# Display7Seg.net
KiCad netlist of a schematic drawn in Altium Designer
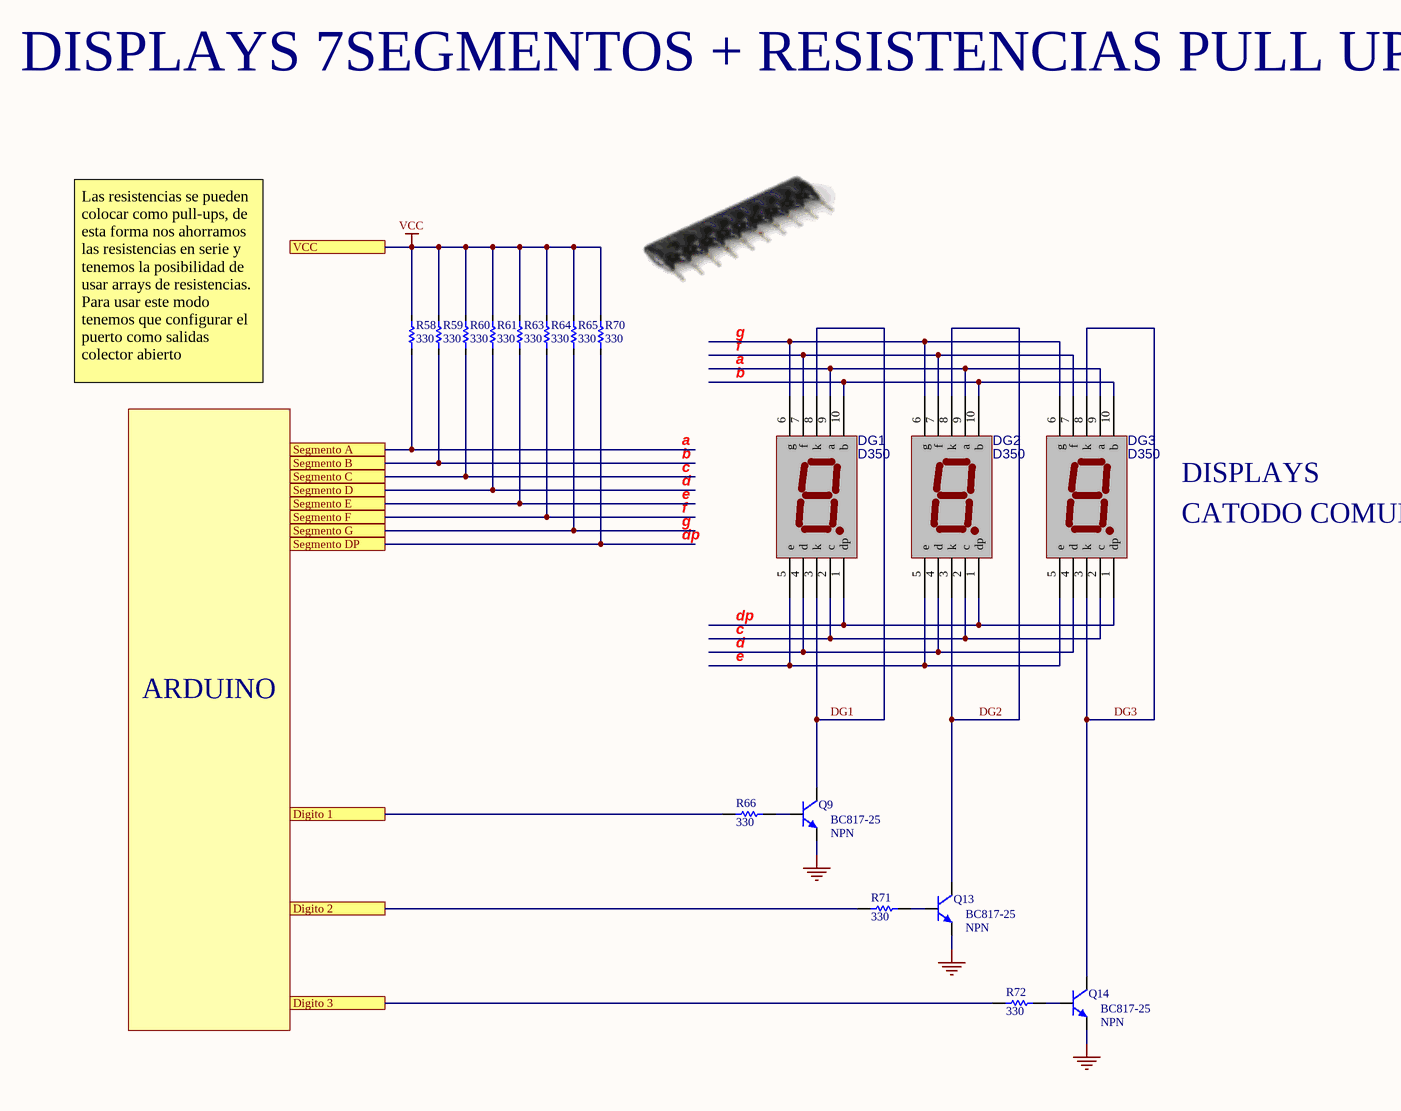
[diagram p0: Display7Seg.SCHDOC]

(export (version "E")
  (design (tool "Eeschema 10.0.6"))
  (components
    (comp (ref "DG1")
      (value "D350")
      (footprint "DISPLAY 7SEG 34x24")
      (description "DIGITO DE 1/2 PULGADA")
      (libsource (lib "*") (part "DGT350"))
    )
    (comp (ref "DG2")
      (value "D350")
      (footprint "DISPLAY 7SEG 34x24")
      (description "DIGITO DE 1/2 PULGADA")
      (libsource (lib "*") (part "DGT350"))
    )
    (comp (ref "DG3")
      (value "D350")
      (footprint "DISPLAY 7SEG 34x24")
      (description "DIGITO DE 1/2 PULGADA")
      (libsource (lib "*") (part "DGT350"))
    )
    (comp (ref "Q9")
      (value "BC817-25")
      (footprint "SOT23-3")
      (description "Transistor NPN")
      (fields
        (field (name "MANUFACTURER") "Fairchild Semiconductor")
        (field (name "PUBLISHER") "Altium Hobart Technology Centre")
      )
      (libsource (lib "DG 128 en Tango SMD") (part "BC817-25"))
    )
    (comp (ref "Q13")
      (value "BC817-25")
      (footprint "SOT23-3")
      (description "Transistor NPN")
      (fields
        (field (name "MANUFACTURER") "Fairchild Semiconductor")
        (field (name "PUBLISHER") "Altium Hobart Technology Centre")
      )
      (libsource (lib "DG 128 en Tango SMD") (part "BC817-25"))
    )
    (comp (ref "Q14")
      (value "BC817-25")
      (footprint "SOT23-3")
      (description "Transistor NPN")
      (fields
        (field (name "MANUFACTURER") "Fairchild Semiconductor")
        (field (name "PUBLISHER") "Altium Hobart Technology Centre")
      )
      (libsource (lib "DG 128 en Tango SMD") (part "BC817-25"))
    )
    (comp (ref "R58")
      (value "330")
      (footprint "0603")
      (description "Resistencia")
      (fields
        (field (name "MANUFACTURER") "Generic Components")
        (field (name "Comment") "470")
        (field (name "PUBLISHER") "Altium Limited")
      )
      (libsource (lib "Universal SCH") (part "Res1"))
    )
    (comp (ref "R59")
      (value "330")
      (footprint "0603")
      (description "Resistencia")
      (fields
        (field (name "MANUFACTURER") "Generic Components")
        (field (name "Comment") "470")
        (field (name "PUBLISHER") "Altium Limited")
      )
      (libsource (lib "Universal SCH") (part "Res1"))
    )
    (comp (ref "R60")
      (value "330")
      (footprint "0603")
      (description "Resistencia")
      (fields
        (field (name "MANUFACTURER") "Generic Components")
        (field (name "Comment") "470")
        (field (name "PUBLISHER") "Altium Limited")
      )
      (libsource (lib "Universal SCH") (part "Res1"))
    )
    (comp (ref "R61")
      (value "330")
      (footprint "0603")
      (description "Resistencia")
      (fields
        (field (name "MANUFACTURER") "Generic Components")
        (field (name "Comment") "470")
        (field (name "PUBLISHER") "Altium Limited")
      )
      (libsource (lib "Universal SCH") (part "Res1"))
    )
    (comp (ref "R63")
      (value "330")
      (footprint "0603")
      (description "Resistencia")
      (fields
        (field (name "MANUFACTURER") "Generic Components")
        (field (name "Comment") "470")
        (field (name "PUBLISHER") "Altium Limited")
      )
      (libsource (lib "Universal SCH") (part "Res1"))
    )
    (comp (ref "R64")
      (value "330")
      (footprint "0603")
      (description "Resistencia")
      (fields
        (field (name "MANUFACTURER") "Generic Components")
        (field (name "Comment") "470")
        (field (name "PUBLISHER") "Altium Limited")
      )
      (libsource (lib "Universal SCH") (part "Res1"))
    )
    (comp (ref "R65")
      (value "330")
      (footprint "0603")
      (description "Resistencia")
      (fields
        (field (name "MANUFACTURER") "Generic Components")
        (field (name "Comment") "470")
        (field (name "PUBLISHER") "Altium Limited")
      )
      (libsource (lib "Universal SCH") (part "Res1"))
    )
    (comp (ref "R66")
      (value "330")
      (footprint "0603")
      (description "Resistencia")
      (fields (field (name "MANUFACTURER") "Generic Components") (field (name "PUBLISHER") "Altium Limited"))
      (libsource (lib "Miscellaneous Devices") (part "Res1"))
    )
    (comp (ref "R70")
      (value "330")
      (footprint "0603")
      (description "Resistencia")
      (fields
        (field (name "MANUFACTURER") "Generic Components")
        (field (name "Comment") "470")
        (field (name "PUBLISHER") "Altium Limited")
      )
      (libsource (lib "Universal SCH") (part "Res1"))
    )
    (comp (ref "R71")
      (value "330")
      (footprint "0603")
      (description "Resistencia")
      (fields (field (name "MANUFACTURER") "Generic Components") (field (name "PUBLISHER") "Altium Limited"))
      (libsource (lib "Miscellaneous Devices") (part "Res1"))
    )
    (comp (ref "R72")
      (value "330")
      (footprint "0603")
      (description "Resistencia")
      (fields (field (name "MANUFACTURER") "Generic Components") (field (name "PUBLISHER") "Altium Limited"))
      (libsource (lib "Miscellaneous Devices") (part "Res1"))
    )
  )
  (nets
    (net (code "1") (name "/DG1") (class "Default")
      (node (ref "DG1") (pin "3") (pinfunction "k_3") (pintype "passive"))
      (node (ref "DG1") (pin "8") (pinfunction "k_8") (pintype "passive"))
      (node (ref "Q9") (pin "3") (pinfunction "C_3") (pintype "passive"))
    )
    (net (code "2") (name "/DG2") (class "Default")
      (node (ref "DG2") (pin "3") (pinfunction "k_3") (pintype "passive"))
      (node (ref "DG2") (pin "8") (pinfunction "k_8") (pintype "passive"))
      (node (ref "Q13") (pin "3") (pinfunction "C_3") (pintype "passive"))
    )
    (net (code "3") (name "/DG3") (class "Default")
      (node (ref "DG3") (pin "3") (pinfunction "k_3") (pintype "passive"))
      (node (ref "DG3") (pin "8") (pinfunction "k_8") (pintype "passive"))
      (node (ref "Q14") (pin "3") (pinfunction "C_3") (pintype "passive"))
    )
    (net (code "4") (name "/Digito 1") (class "Default")
      (node (ref "R66") (pin "1") (pinfunction "1_1") (pintype "passive"))
    )
    (net (code "5") (name "/Digito 2") (class "Default")
      (node (ref "R71") (pin "1") (pinfunction "1_1") (pintype "passive"))
    )
    (net (code "6") (name "/Digito 3") (class "Default")
      (node (ref "R72") (pin "1") (pinfunction "1_1") (pintype "passive"))
    )
    (net (code "7") (name "/a") (class "Default")
      (node (ref "DG1") (pin "9") (pinfunction "a_9") (pintype "passive"))
      (node (ref "DG2") (pin "9") (pinfunction "a_9") (pintype "passive"))
      (node (ref "DG3") (pin "9") (pinfunction "a_9") (pintype "passive"))
      (node (ref "R58") (pin "2") (pinfunction "2_2") (pintype "passive"))
    )
    (net (code "8") (name "/b") (class "Default")
      (node (ref "DG1") (pin "10") (pinfunction "b_10") (pintype "passive"))
      (node (ref "DG2") (pin "10") (pinfunction "b_10") (pintype "passive"))
      (node (ref "DG3") (pin "10") (pinfunction "b_10") (pintype "passive"))
      (node (ref "R59") (pin "2") (pinfunction "2_2") (pintype "passive"))
    )
    (net (code "9") (name "/c") (class "Default")
      (node (ref "DG1") (pin "2") (pinfunction "c_2") (pintype "passive"))
      (node (ref "DG2") (pin "2") (pinfunction "c_2") (pintype "passive"))
      (node (ref "DG3") (pin "2") (pinfunction "c_2") (pintype "passive"))
      (node (ref "R60") (pin "2") (pinfunction "2_2") (pintype "passive"))
    )
    (net (code "10") (name "/d") (class "Default")
      (node (ref "DG1") (pin "4") (pinfunction "d_4") (pintype "passive"))
      (node (ref "DG2") (pin "4") (pinfunction "d_4") (pintype "passive"))
      (node (ref "DG3") (pin "4") (pinfunction "d_4") (pintype "passive"))
      (node (ref "R61") (pin "2") (pinfunction "2_2") (pintype "passive"))
    )
    (net (code "11") (name "/dp") (class "Default")
      (node (ref "DG1") (pin "1") (pinfunction "dp_1") (pintype "passive"))
      (node (ref "DG2") (pin "1") (pinfunction "dp_1") (pintype "passive"))
      (node (ref "DG3") (pin "1") (pinfunction "dp_1") (pintype "passive"))
      (node (ref "R70") (pin "2") (pinfunction "2_2") (pintype "passive"))
    )
    (net (code "12") (name "/e") (class "Default")
      (node (ref "DG1") (pin "5") (pinfunction "e_5") (pintype "passive"))
      (node (ref "DG2") (pin "5") (pinfunction "e_5") (pintype "passive"))
      (node (ref "DG3") (pin "5") (pinfunction "e_5") (pintype "passive"))
      (node (ref "R63") (pin "2") (pinfunction "2_2") (pintype "passive"))
    )
    (net (code "13") (name "/f") (class "Default")
      (node (ref "DG1") (pin "7") (pinfunction "f_7") (pintype "passive"))
      (node (ref "DG2") (pin "7") (pinfunction "f_7") (pintype "passive"))
      (node (ref "DG3") (pin "7") (pinfunction "f_7") (pintype "passive"))
      (node (ref "R64") (pin "2") (pinfunction "2_2") (pintype "passive"))
    )
    (net (code "14") (name "/g") (class "Default")
      (node (ref "DG1") (pin "6") (pinfunction "g_6") (pintype "passive"))
      (node (ref "DG2") (pin "6") (pinfunction "g_6") (pintype "passive"))
      (node (ref "DG3") (pin "6") (pinfunction "g_6") (pintype "passive"))
      (node (ref "R65") (pin "2") (pinfunction "2_2") (pintype "passive"))
    )
    (net (code "15") (name "GND") (class "Default")
      (node (ref "Q13") (pin "2") (pinfunction "E_2") (pintype "passive"))
      (node (ref "Q14") (pin "2") (pinfunction "E_2") (pintype "passive"))
      (node (ref "Q9") (pin "2") (pinfunction "E_2") (pintype "passive"))
    )
    (net (code "16") (name "Net-(Q9-B)") (class "Default")
      (node (ref "Q9") (pin "1") (pinfunction "B_1") (pintype "passive"))
      (node (ref "R66") (pin "2") (pinfunction "2_2") (pintype "passive"))
    )
    (net (code "17") (name "Net-(Q13-B)") (class "Default")
      (node (ref "Q13") (pin "1") (pinfunction "B_1") (pintype "passive"))
      (node (ref "R71") (pin "2") (pinfunction "2_2") (pintype "passive"))
    )
    (net (code "18") (name "Net-(Q14-B)") (class "Default")
      (node (ref "Q14") (pin "1") (pinfunction "B_1") (pintype "passive"))
      (node (ref "R72") (pin "2") (pinfunction "2_2") (pintype "passive"))
    )
    (net (code "19") (name "VCC") (class "Default")
      (node (ref "R58") (pin "1") (pinfunction "1_1") (pintype "passive"))
      (node (ref "R59") (pin "1") (pinfunction "1_1") (pintype "passive"))
      (node (ref "R60") (pin "1") (pinfunction "1_1") (pintype "passive"))
      (node (ref "R61") (pin "1") (pinfunction "1_1") (pintype "passive"))
      (node (ref "R63") (pin "1") (pinfunction "1_1") (pintype "passive"))
      (node (ref "R64") (pin "1") (pinfunction "1_1") (pintype "passive"))
      (node (ref "R65") (pin "1") (pinfunction "1_1") (pintype "passive"))
      (node (ref "R70") (pin "1") (pinfunction "1_1") (pintype "passive"))
    )
  )
)
